# didah.net
KiCad netlist of a schematic drawn in EAGLE
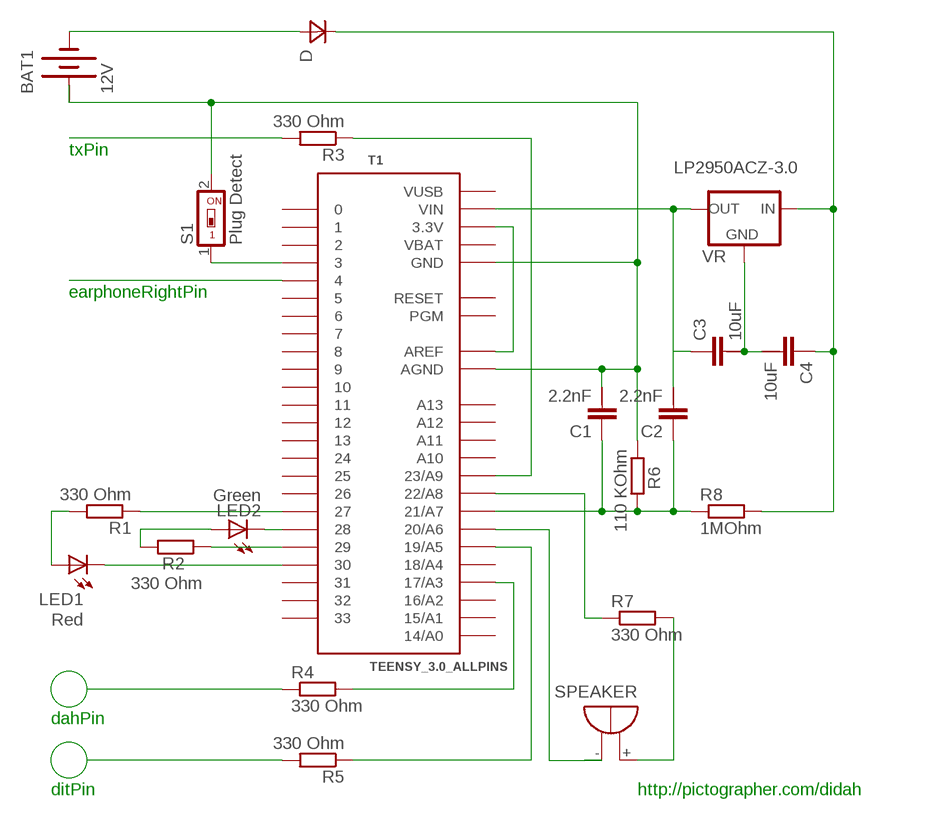
[diagram p0: schematic, sheet 1]

(export (version "E")
  (design (tool "Eeschema 10.0.6"))
  (components
    (comp (ref "BAT1")
      (value "12V")
      (footprint "eagle-import:BATTERY")
      (libsource (lib "eagle-import") (part "BATTERY"))
    )
    (comp (ref "C1")
      (value "2.2nF")
      (footprint "eagle-import:C2.5_5-6")
      (libsource (lib "eagle-import") (part "C-2.5-5/6"))
    )
    (comp (ref "C2")
      (value "2.2nF")
      (footprint "eagle-import:C2.5_5-6")
      (libsource (lib "eagle-import") (part "C-2.5-5/6"))
    )
    (comp (ref "C3")
      (value "10uF")
      (footprint "eagle-import:C2.5_5-6")
      (libsource (lib "eagle-import") (part "C-2.5-5/6"))
    )
    (comp (ref "C4")
      (value "10uF")
      (footprint "eagle-import:C2.5_5-6")
      (libsource (lib "eagle-import") (part "C-2.5-5/6"))
    )
    (comp (ref "D")
      (value "DIODE")
      (footprint "eagle-import:DIODE")
      (libsource (lib "eagle-import") (part "DIODE"))
    )
    (comp (ref "LED1")
      (value "Red")
      (footprint "eagle-import:LED_SML0603")
      (libsource (lib "eagle-import") (part "LED_ESML0603"))
    )
    (comp (ref "LED2")
      (value "Green")
      (footprint "eagle-import:LED_SML0603")
      (libsource (lib "eagle-import") (part "LED_ESML0603"))
    )
    (comp (ref "R1")
      (value "330 Ohm")
      (footprint "eagle-import:R0402")
      (libsource (lib "eagle-import") (part "RR0402"))
    )
    (comp (ref "R2")
      (value "330 Ohm")
      (footprint "eagle-import:R0402")
      (libsource (lib "eagle-import") (part "RR0402"))
    )
    (comp (ref "R3")
      (value "330 Ohm")
      (footprint "eagle-import:R0402")
      (libsource (lib "eagle-import") (part "RR0402"))
    )
    (comp (ref "R4")
      (value "330 Ohm")
      (footprint "eagle-import:R0402")
      (libsource (lib "eagle-import") (part "RR0402"))
    )
    (comp (ref "R5")
      (value "330 Ohm")
      (footprint "eagle-import:R0402")
      (libsource (lib "eagle-import") (part "RR0402"))
    )
    (comp (ref "R6")
      (value "110 KOhm")
      (footprint "eagle-import:0204_7")
      (libsource (lib "eagle-import") (part "R0204/7"))
    )
    (comp (ref "R7")
      (value "330 Ohm")
      (footprint "eagle-import:R0402")
      (libsource (lib "eagle-import") (part "RR0402"))
    )
    (comp (ref "R8")
      (value "1MOhm")
      (footprint "eagle-import:0204_7")
      (libsource (lib "eagle-import") (part "R0204/7"))
    )
    (comp (ref "S1")
      (value "Plug Detect")
      (footprint "eagle-import:SMS-001")
      (libsource (lib "eagle-import") (part "SWS001"))
    )
    (comp (ref "SPEAKER")
      (value "BMT1205XH7.5")
      (footprint "eagle-import:BMT1205XH7.5")
      (libsource (lib "eagle-import") (part "BMT1205XH7.5"))
    )
    (comp (ref "T1")
      (value "TEENSY_3.0_ALLPINS")
      (footprint "eagle-import:TEENSY_3.0_ALLPINS")
      (libsource (lib "eagle-import") (part "TEENSY_3.0_ALLPINS"))
    )
    (comp (ref "VR")
      (value "LP2950ACZ-3.0")
      (footprint "eagle-import:TO92")
      (libsource (lib "eagle-import") (part "LP2950?ACZ-3.0"))
    )
  )
  (nets
    (net (code "1") (name "/VBAT") (class "Default")
      (node (ref "T1") (pin "VBAT") (pinfunction "VBAT_VBAT") (pintype "power_in"))
    )
    (net (code "2") (name "/VUSB") (class "Default")
      (node (ref "T1") (pin "VUSB") (pinfunction "VUSB_VUSB") (pintype "power_in"))
    )
    (net (code "3") (name "Net-(BAT1-+-Pad+@1)") (class "Default")
      (node (ref "BAT1") (pin "+") (pinfunction "+_+") (pintype "power_in"))
      (node (ref "BAT1") (pin "+@1") (pinfunction "+_+@1") (pintype "power_in"))
      (node (ref "C1") (pin "2") (pinfunction "2_2") (pintype "passive"))
      (node (ref "R6") (pin "1") (pinfunction "1_1") (pintype "passive"))
      (node (ref "S1") (pin "2") (pinfunction "2_2") (pintype "passive"))
      (node (ref "T1") (pin "AGND") (pinfunction "AGND_AGND") (pintype "power_in"))
      (node (ref "T1") (pin "GND") (pinfunction "GND_GND") (pintype "power_in"))
      (node (ref "T1") (pin "GND1") (pinfunction "GND_GND1") (pintype "power_in"))
      (node (ref "T1") (pin "GND2") (pinfunction "GND_GND2") (pintype "power_in"))
    )
    (net (code "4") (name "Net-(BAT1-Pad-)") (class "Default")
      (node (ref "BAT1") (pin "-") (pinfunction "-_-") (pintype "power_in"))
      (node (ref "D") (pin "C") (pinfunction "C_C") (pintype "input"))
    )
    (net (code "5") (name "Net-(C1-Pad1)") (class "Default")
      (node (ref "C1") (pin "1") (pinfunction "1_1") (pintype "passive"))
      (node (ref "C2") (pin "1") (pinfunction "1_1") (pintype "passive"))
      (node (ref "R6") (pin "2") (pinfunction "2_2") (pintype "passive"))
      (node (ref "R8") (pin "1") (pinfunction "1_1") (pintype "passive"))
      (node (ref "T1") (pin "21/A7") (pinfunction "21/A7_21/A7") (pintype "bidirectional"))
    )
    (net (code "6") (name "Net-(LED1-PadA)") (class "Default")
      (node (ref "LED1") (pin "A") (pinfunction "A_A") (pintype "passive"))
      (node (ref "R1") (pin "2") (pinfunction "2_2") (pintype "passive"))
    )
    (net (code "7") (name "Net-(LED1-PadC)") (class "Default")
      (node (ref "LED1") (pin "C") (pinfunction "C_C") (pintype "passive"))
      (node (ref "T1") (pin "30") (pinfunction "30_30") (pintype "bidirectional"))
    )
    (net (code "8") (name "Net-(LED2-PadA)") (class "Default")
      (node (ref "LED2") (pin "A") (pinfunction "A_A") (pintype "passive"))
      (node (ref "R2") (pin "2") (pinfunction "2_2") (pintype "passive"))
    )
    (net (code "9") (name "Net-(LED2-PadC)") (class "Default")
      (node (ref "LED2") (pin "C") (pinfunction "C_C") (pintype "passive"))
      (node (ref "T1") (pin "28") (pinfunction "28_28") (pintype "bidirectional"))
    )
    (net (code "10") (name "Net-(R1-Pad1)") (class "Default")
      (node (ref "R1") (pin "1") (pinfunction "1_1") (pintype "passive"))
      (node (ref "T1") (pin "27") (pinfunction "27_27") (pintype "bidirectional"))
    )
    (net (code "11") (name "Net-(R2-Pad1)") (class "Default")
      (node (ref "R2") (pin "1") (pinfunction "1_1") (pintype "passive"))
      (node (ref "T1") (pin "29") (pinfunction "29_29") (pintype "bidirectional"))
    )
    (net (code "12") (name "Net-(R3-Pad1)") (class "Default")
      (node (ref "R3") (pin "1") (pinfunction "1_1") (pintype "passive"))
      (node (ref "T1") (pin "23/A9") (pinfunction "23/A9_23/A9") (pintype "bidirectional"))
    )
    (net (code "13") (name "Net-(R4-Pad2)") (class "Default")
      (node (ref "R4") (pin "2") (pinfunction "2_2") (pintype "passive"))
      (node (ref "T1") (pin "17/A3") (pinfunction "17/A3_17/A3") (pintype "bidirectional"))
    )
    (net (code "14") (name "Net-(R5-Pad1)") (class "Default")
      (node (ref "R5") (pin "1") (pinfunction "1_1") (pintype "passive"))
      (node (ref "T1") (pin "19/A5") (pinfunction "19/A5_19/A5") (pintype "bidirectional"))
    )
    (net (code "15") (name "Net-(R7-Pad1)") (class "Default")
      (node (ref "R7") (pin "1") (pinfunction "1_1") (pintype "passive"))
      (node (ref "T1") (pin "22/A8") (pinfunction "22/A8_22/A8") (pintype "bidirectional"))
    )
    (net (code "16") (name "Net-(R7-Pad2)") (class "Default")
      (node (ref "R7") (pin "2") (pinfunction "2_2") (pintype "passive"))
      (node (ref "SPEAKER") (pin "+") (pinfunction "+_+") (pintype "passive"))
    )
    (net (code "17") (name "Net-(S1-Pad1)") (class "Default")
      (node (ref "S1") (pin "1") (pinfunction "1_1") (pintype "passive"))
      (node (ref "T1") (pin "3") (pinfunction "3_3") (pintype "bidirectional"))
    )
    (net (code "18") (name "Net-(SPEAKER-Pad-)") (class "Default")
      (node (ref "SPEAKER") (pin "-") (pinfunction "-_-") (pintype "passive"))
      (node (ref "T1") (pin "20/A6") (pinfunction "20/A6_20/A6") (pintype "bidirectional"))
    )
    (net (code "19") (name "Net-(T1-3.3V-Pad3.3V1)") (class "Default")
      (node (ref "T1") (pin "3.3V") (pinfunction "3.3V_3.3V") (pintype "power_in"))
      (node (ref "T1") (pin "3.3V1") (pinfunction "3.3V_3.3V1") (pintype "power_in"))
      (node (ref "T1") (pin "3.3V2") (pinfunction "3.3V_3.3V2") (pintype "power_in"))
      (node (ref "T1") (pin "AREF") (pinfunction "AREF_AREF") (pintype "power_in"))
    )
    (net (code "20") (name "Net-(VR-GND)") (class "Default")
      (node (ref "C3") (pin "2") (pinfunction "2_2") (pintype "passive"))
      (node (ref "C4") (pin "2") (pinfunction "2_2") (pintype "passive"))
      (node (ref "VR") (pin "2") (pinfunction "GND_2") (pintype "input"))
    )
    (net (code "21") (name "Net-(VR-IN)") (class "Default")
      (node (ref "C4") (pin "1") (pinfunction "1_1") (pintype "passive"))
      (node (ref "D") (pin "A") (pinfunction "A_A") (pintype "input"))
      (node (ref "R8") (pin "2") (pinfunction "2_2") (pintype "passive"))
      (node (ref "VR") (pin "3") (pinfunction "IN_3") (pintype "input"))
    )
    (net (code "22") (name "Net-(VR-OUT)") (class "Default")
      (node (ref "C2") (pin "2") (pinfunction "2_2") (pintype "passive"))
      (node (ref "C3") (pin "1") (pinfunction "1_1") (pintype "passive"))
      (node (ref "T1") (pin "VIN") (pinfunction "VIN_VIN") (pintype "power_in"))
      (node (ref "VR") (pin "1") (pinfunction "OUT_1") (pintype "passive"))
    )
    (net (code "23") (name "unconnected-(C1-Pad3)") (class "Default")
      (node (ref "C1") (pin "3") (pinfunction "3_3") (pintype "passive"))
    )
    (net (code "24") (name "unconnected-(C2-Pad3)") (class "Default")
      (node (ref "C2") (pin "3") (pinfunction "3_3") (pintype "passive"))
    )
    (net (code "25") (name "unconnected-(C3-Pad3)") (class "Default")
      (node (ref "C3") (pin "3") (pinfunction "3_3") (pintype "passive"))
    )
    (net (code "26") (name "unconnected-(C4-Pad3)") (class "Default")
      (node (ref "C4") (pin "3") (pinfunction "3_3") (pintype "passive"))
    )
    (net (code "27") (name "unconnected-(R3-Pad2)") (class "Default")
      (node (ref "R3") (pin "2") (pinfunction "2_2") (pintype "passive"))
    )
    (net (code "28") (name "unconnected-(R4-Pad1)") (class "Default")
      (node (ref "R4") (pin "1") (pinfunction "1_1") (pintype "passive"))
    )
    (net (code "29") (name "unconnected-(R5-Pad2)") (class "Default")
      (node (ref "R5") (pin "2") (pinfunction "2_2") (pintype "passive"))
    )
    (net (code "30") (name "unconnected-(T1-Pad0)") (class "Default")
      (node (ref "T1") (pin "0") (pinfunction "0_0") (pintype "bidirectional"))
    )
    (net (code "31") (name "unconnected-(T1-Pad1)") (class "Default")
      (node (ref "T1") (pin "1") (pinfunction "1_1") (pintype "bidirectional"))
    )
    (net (code "32") (name "unconnected-(T1-Pad2)") (class "Default")
      (node (ref "T1") (pin "2") (pinfunction "2_2") (pintype "bidirectional"))
    )
    (net (code "33") (name "unconnected-(T1-Pad4)") (class "Default")
      (node (ref "T1") (pin "4") (pinfunction "4_4") (pintype "bidirectional"))
    )
    (net (code "34") (name "unconnected-(T1-Pad5)") (class "Default")
      (node (ref "T1") (pin "5") (pinfunction "5_5") (pintype "bidirectional"))
    )
    (net (code "35") (name "unconnected-(T1-Pad6)") (class "Default")
      (node (ref "T1") (pin "6") (pinfunction "6_6") (pintype "bidirectional"))
    )
    (net (code "36") (name "unconnected-(T1-Pad7)") (class "Default")
      (node (ref "T1") (pin "7") (pinfunction "7_7") (pintype "bidirectional"))
    )
    (net (code "37") (name "unconnected-(T1-Pad8)") (class "Default")
      (node (ref "T1") (pin "8") (pinfunction "8_8") (pintype "bidirectional"))
    )
    (net (code "38") (name "unconnected-(T1-Pad9)") (class "Default")
      (node (ref "T1") (pin "9") (pinfunction "9_9") (pintype "bidirectional"))
    )
    (net (code "39") (name "unconnected-(T1-Pad10)") (class "Default")
      (node (ref "T1") (pin "10") (pinfunction "10_10") (pintype "bidirectional"))
    )
    (net (code "40") (name "unconnected-(T1-Pad11)") (class "Default")
      (node (ref "T1") (pin "11") (pinfunction "11_11") (pintype "bidirectional"))
    )
    (net (code "41") (name "unconnected-(T1-Pad12)") (class "Default")
      (node (ref "T1") (pin "12") (pinfunction "12_12") (pintype "bidirectional"))
    )
    (net (code "42") (name "unconnected-(T1-Pad13)") (class "Default")
      (node (ref "T1") (pin "13") (pinfunction "13_13") (pintype "bidirectional"))
    )
    (net (code "43") (name "unconnected-(T1-Pad14{slash}A0)") (class "Default")
      (node (ref "T1") (pin "14/A0") (pinfunction "14/A0_14/A0") (pintype "bidirectional"))
    )
    (net (code "44") (name "unconnected-(T1-Pad15{slash}A1)") (class "Default")
      (node (ref "T1") (pin "15/A1") (pinfunction "15/A1_15/A1") (pintype "bidirectional"))
    )
    (net (code "45") (name "unconnected-(T1-Pad16{slash}A2)") (class "Default")
      (node (ref "T1") (pin "16/A2") (pinfunction "16/A2_16/A2") (pintype "bidirectional"))
    )
    (net (code "46") (name "unconnected-(T1-Pad18{slash}A4)") (class "Default")
      (node (ref "T1") (pin "18/A4") (pinfunction "18/A4_18/A4") (pintype "bidirectional"))
    )
    (net (code "47") (name "unconnected-(T1-Pad24)") (class "Default")
      (node (ref "T1") (pin "24") (pinfunction "24_24") (pintype "bidirectional"))
    )
    (net (code "48") (name "unconnected-(T1-Pad25)") (class "Default")
      (node (ref "T1") (pin "25") (pinfunction "25_25") (pintype "bidirectional"))
    )
    (net (code "49") (name "unconnected-(T1-Pad26)") (class "Default")
      (node (ref "T1") (pin "26") (pinfunction "26_26") (pintype "bidirectional"))
    )
    (net (code "50") (name "unconnected-(T1-Pad31)") (class "Default")
      (node (ref "T1") (pin "31") (pinfunction "31_31") (pintype "bidirectional"))
    )
    (net (code "51") (name "unconnected-(T1-Pad32)") (class "Default")
      (node (ref "T1") (pin "32") (pinfunction "32_32") (pintype "bidirectional"))
    )
    (net (code "52") (name "unconnected-(T1-Pad33)") (class "Default")
      (node (ref "T1") (pin "33") (pinfunction "33_33") (pintype "bidirectional"))
    )
    (net (code "53") (name "unconnected-(T1-PadA10)") (class "Default")
      (node (ref "T1") (pin "A10") (pinfunction "A10_A10") (pintype "bidirectional"))
    )
    (net (code "54") (name "unconnected-(T1-PadA11)") (class "Default")
      (node (ref "T1") (pin "A11") (pinfunction "A11_A11") (pintype "bidirectional"))
    )
    (net (code "55") (name "unconnected-(T1-PadA12)") (class "Default")
      (node (ref "T1") (pin "A12") (pinfunction "A12_A12") (pintype "bidirectional"))
    )
    (net (code "56") (name "unconnected-(T1-PadA13)") (class "Default")
      (node (ref "T1") (pin "A13") (pinfunction "A13_A13") (pintype "bidirectional"))
    )
    (net (code "57") (name "unconnected-(T1-PadPGM)") (class "Default")
      (node (ref "T1") (pin "PGM") (pinfunction "PGM_PGM") (pintype "bidirectional"))
    )
    (net (code "58") (name "unconnected-(T1-PadRESET)") (class "Default")
      (node (ref "T1") (pin "RESET") (pinfunction "RESET_RESET") (pintype "bidirectional"))
    )
  )
)
